# SPE_PHY.net
KiCad netlist of a schematic drawn in Altium Designer
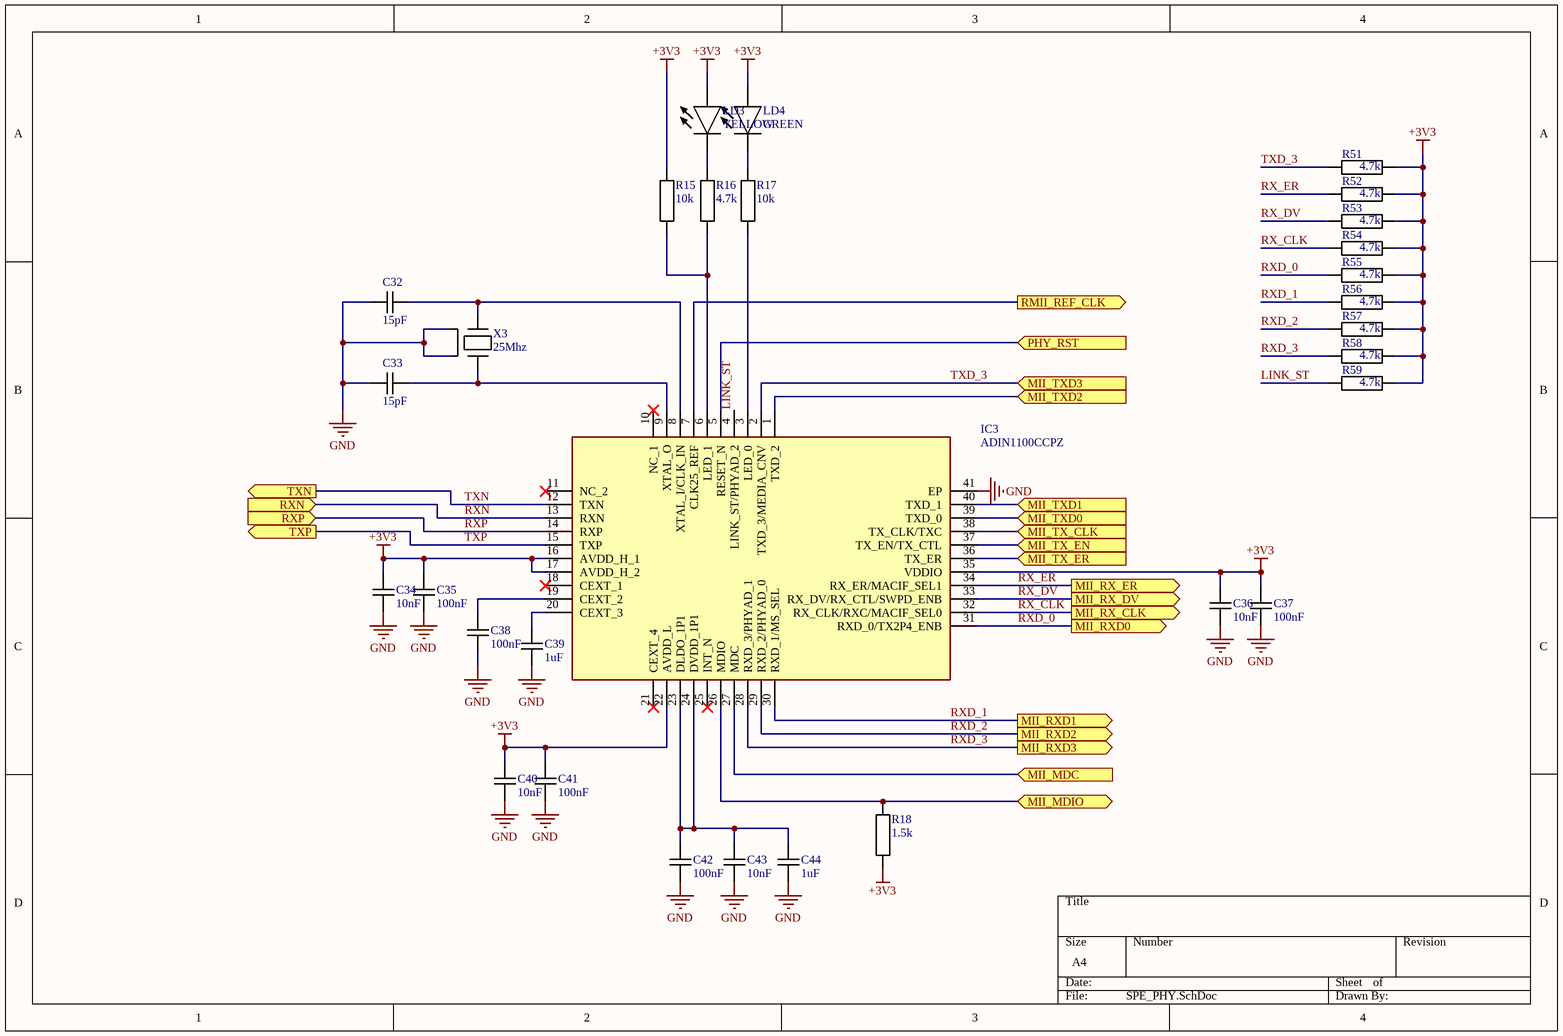
[diagram p0: SPE_PHY.SchDoc]

(export (version "E")
  (design (tool "Eeschema 10.0.6"))
  (components
    (comp (ref "C32")
      (value "15pF")
      (footprint "CAPACITOR 1608 REFLOW")
      (description "Capacitor")
      (libsource (lib "Capacitor") (part "Capacitor"))
    )
    (comp (ref "C33")
      (value "15pF")
      (footprint "CAPACITOR 1608 REFLOW")
      (description "Capacitor")
      (libsource (lib "Capacitor") (part "Capacitor"))
    )
    (comp (ref "C34")
      (value "10nF")
      (footprint "CAPACITOR 1608 REFLOW")
      (description "Capacitor")
      (libsource (lib "Capacitor") (part "Capacitor"))
    )
    (comp (ref "C35")
      (value "100nF")
      (footprint "CAPACITOR 1608 REFLOW")
      (description "Capacitor")
      (libsource (lib "Capacitor") (part "Capacitor"))
    )
    (comp (ref "C36")
      (value "10nF")
      (footprint "CAPACITOR 1608 REFLOW")
      (description "Capacitor")
      (libsource (lib "Capacitor") (part "Capacitor"))
    )
    (comp (ref "C37")
      (value "100nF")
      (footprint "CAPACITOR 1608 REFLOW")
      (description "Capacitor")
      (libsource (lib "Capacitor") (part "Capacitor"))
    )
    (comp (ref "C38")
      (value "100nF")
      (footprint "CAPACITOR 1608 REFLOW")
      (description "Capacitor")
      (libsource (lib "Capacitor") (part "Capacitor"))
    )
    (comp (ref "C39")
      (value "1uF")
      (footprint "CAPACITOR 1608 REFLOW")
      (description "Capacitor")
      (libsource (lib "Capacitor") (part "Capacitor"))
    )
    (comp (ref "C40")
      (value "10nF")
      (footprint "CAPACITOR 1608 REFLOW")
      (description "Capacitor")
      (libsource (lib "Capacitor") (part "Capacitor"))
    )
    (comp (ref "C41")
      (value "100nF")
      (footprint "CAPACITOR 1608 REFLOW")
      (description "Capacitor")
      (libsource (lib "Capacitor") (part "Capacitor"))
    )
    (comp (ref "C42")
      (value "100nF")
      (footprint "CAPACITOR 1608 REFLOW")
      (description "Capacitor")
      (libsource (lib "Capacitor") (part "Capacitor"))
    )
    (comp (ref "C43")
      (value "10nF")
      (footprint "CAPACITOR 1608 REFLOW")
      (description "Capacitor")
      (libsource (lib "Capacitor") (part "Capacitor"))
    )
    (comp (ref "C44")
      (value "1uF")
      (footprint "CAPACITOR 1608 REFLOW")
      (description "Capacitor")
      (libsource (lib "Capacitor") (part "Capacitor"))
    )
    (comp (ref "IC3")
      (value "ADIN1100CCPZ")
      (footprint "QFN50P600X600X80-41N-D")
      (description "Integrated Circuit")
      (fields (field (name "MOUSER PART NUMBER") "584-ADIN1100CCPZ"))
      (libsource (lib "*") (part "ADIN1100CCPZ"))
    )
    (comp (ref "LD3")
      (value "YELLOW")
      (footprint "LED 1608 REFLOW")
      (description "LED generic")
      (libsource (lib "Diode") (part "LED"))
    )
    (comp (ref "LD4")
      (value "GREEN")
      (footprint "LED 1608 REFLOW")
      (description "LED generic")
      (libsource (lib "Diode") (part "LED"))
    )
    (comp (ref "R15")
      (value "10k")
      (footprint "RESISTOR 1608 REFLOW")
      (description "Resistor")
      (libsource (lib "Resistor") (part "Resistor"))
    )
    (comp (ref "R16")
      (value "4.7k")
      (footprint "RESISTOR 1608 REFLOW")
      (description "Resistor")
      (libsource (lib "Resistor") (part "Resistor"))
    )
    (comp (ref "R17")
      (value "10k")
      (footprint "RESISTOR 1608 REFLOW")
      (description "Resistor")
      (libsource (lib "Resistor") (part "Resistor"))
    )
    (comp (ref "R18")
      (value "1.5k")
      (footprint "RESISTOR 1608 REFLOW")
      (description "Resistor")
      (libsource (lib "Resistor") (part "Resistor"))
    )
    (comp (ref "R51")
      (value "4.7k")
      (footprint "RESISTOR 1608 REFLOW")
      (description "Resistor")
      (libsource (lib "Resistor") (part "Resistor"))
    )
    (comp (ref "R52")
      (value "4.7k")
      (footprint "RESISTOR 1608 REFLOW")
      (description "Resistor")
      (libsource (lib "Resistor") (part "Resistor"))
    )
    (comp (ref "R53")
      (value "4.7k")
      (footprint "RESISTOR 1608 REFLOW")
      (description "Resistor")
      (libsource (lib "Resistor") (part "Resistor"))
    )
    (comp (ref "R54")
      (value "4.7k")
      (footprint "RESISTOR 1608 REFLOW")
      (description "Resistor")
      (libsource (lib "Resistor") (part "Resistor"))
    )
    (comp (ref "R55")
      (value "4.7k")
      (footprint "RESISTOR 1608 REFLOW")
      (description "Resistor")
      (libsource (lib "Resistor") (part "Resistor"))
    )
    (comp (ref "R56")
      (value "4.7k")
      (footprint "RESISTOR 1608 REFLOW")
      (description "Resistor")
      (libsource (lib "Resistor") (part "Resistor"))
    )
    (comp (ref "R57")
      (value "4.7k")
      (footprint "RESISTOR 1608 REFLOW")
      (description "Resistor")
      (libsource (lib "Resistor") (part "Resistor"))
    )
    (comp (ref "R58")
      (value "4.7k")
      (footprint "RESISTOR 1608 REFLOW")
      (description "Resistor")
      (libsource (lib "Resistor") (part "Resistor"))
    )
    (comp (ref "R59")
      (value "4.7k")
      (footprint "RESISTOR 1608 REFLOW")
      (description "Resistor")
      (libsource (lib "Resistor") (part "Resistor"))
    )
    (comp (ref "X3")
      (value "25Mhz")
      (footprint "Crystal C2.5x2 Seiko Epson FA-128")
      (description "Crystal C2.5x2 Seiko Epson FA-128")
      (libsource (lib "Oscillator") (part "Crystal C2.5x2 Seiko Epson FA-128"))
    )
  )
  (nets
    (net (code "1") (name "+3V3") (class "Default")
      (node (ref "C34") (pin "2") (pinfunction "2_2") (pintype "passive"))
      (node (ref "C35") (pin "2") (pinfunction "2_2") (pintype "passive"))
      (node (ref "C36") (pin "2") (pinfunction "2_2") (pintype "passive"))
      (node (ref "C37") (pin "2") (pinfunction "2_2") (pintype "passive"))
      (node (ref "C40") (pin "2") (pinfunction "2_2") (pintype "passive"))
      (node (ref "C41") (pin "2") (pinfunction "2_2") (pintype "passive"))
      (node (ref "IC3") (pin "16") (pinfunction "AVDD_H_1_16") (pintype "passive"))
      (node (ref "IC3") (pin "17") (pinfunction "AVDD_H_2_17") (pintype "passive"))
      (node (ref "IC3") (pin "22") (pinfunction "AVDD_L_22") (pintype "passive"))
      (node (ref "IC3") (pin "35") (pinfunction "VDDIO_35") (pintype "passive"))
      (node (ref "LD3") (pin "2") (pinfunction "A_2") (pintype "passive"))
      (node (ref "LD4") (pin "2") (pinfunction "A_2") (pintype "passive"))
      (node (ref "R15") (pin "2") (pinfunction "2_2") (pintype "passive"))
      (node (ref "R18") (pin "1") (pinfunction "1_1") (pintype "passive"))
      (node (ref "R51") (pin "1") (pinfunction "1_1") (pintype "passive"))
      (node (ref "R52") (pin "1") (pinfunction "1_1") (pintype "passive"))
      (node (ref "R53") (pin "1") (pinfunction "1_1") (pintype "passive"))
      (node (ref "R54") (pin "1") (pinfunction "1_1") (pintype "passive"))
      (node (ref "R55") (pin "1") (pinfunction "1_1") (pintype "passive"))
      (node (ref "R56") (pin "1") (pinfunction "1_1") (pintype "passive"))
      (node (ref "R57") (pin "1") (pinfunction "1_1") (pintype "passive"))
      (node (ref "R58") (pin "1") (pinfunction "1_1") (pintype "passive"))
      (node (ref "R59") (pin "1") (pinfunction "1_1") (pintype "passive"))
    )
    (net (code "2") (name "/LINK_ST") (class "Default")
      (node (ref "IC3") (pin "4") (pinfunction "LINK_ST/PHYAD_2_4") (pintype "passive"))
      (node (ref "R59") (pin "2") (pinfunction "2_2") (pintype "passive"))
    )
    (net (code "3") (name "/MII_MDC") (class "Default")
      (node (ref "IC3") (pin "27") (pinfunction "MDC_27") (pintype "passive"))
    )
    (net (code "4") (name "/MII_MDIO") (class "Default")
      (node (ref "IC3") (pin "26") (pinfunction "MDIO_26") (pintype "passive"))
      (node (ref "R18") (pin "2") (pinfunction "2_2") (pintype "passive"))
    )
    (net (code "5") (name "/MII_TXD0") (class "Default")
      (node (ref "IC3") (pin "39") (pinfunction "TXD_0_39") (pintype "passive"))
    )
    (net (code "6") (name "/MII_TXD1") (class "Default")
      (node (ref "IC3") (pin "40") (pinfunction "TXD_1_40") (pintype "passive"))
    )
    (net (code "7") (name "/MII_TXD2") (class "Default")
      (node (ref "IC3") (pin "1") (pinfunction "TXD_2_1") (pintype "passive"))
    )
    (net (code "8") (name "/MII_TX_CLK") (class "Default")
      (node (ref "IC3") (pin "38") (pinfunction "TX_CLK/TXC_38") (pintype "passive"))
    )
    (net (code "9") (name "/MII_TX_EN") (class "Default")
      (node (ref "IC3") (pin "37") (pinfunction "TX_EN/TX_CTL_37") (pintype "passive"))
    )
    (net (code "10") (name "/MII_TX_ER") (class "Default")
      (node (ref "IC3") (pin "36") (pinfunction "TX_ER_36") (pintype "passive"))
    )
    (net (code "11") (name "/PHY_RST") (class "Default")
      (node (ref "IC3") (pin "5") (pinfunction "RESET_N_5") (pintype "passive"))
    )
    (net (code "12") (name "/RMII_REF_CLK") (class "Default")
      (node (ref "IC3") (pin "7") (pinfunction "CLK25_REF_7") (pintype "passive"))
    )
    (net (code "13") (name "/RXD_0") (class "Default")
      (node (ref "IC3") (pin "31") (pinfunction "RXD_0/TX2P4_ENB_31") (pintype "passive"))
      (node (ref "R55") (pin "2") (pinfunction "2_2") (pintype "passive"))
    )
    (net (code "14") (name "/RXD_1") (class "Default")
      (node (ref "IC3") (pin "30") (pinfunction "RXD_1/MS_SEL_30") (pintype "passive"))
      (node (ref "R56") (pin "2") (pinfunction "2_2") (pintype "passive"))
    )
    (net (code "15") (name "/RXD_2") (class "Default")
      (node (ref "IC3") (pin "29") (pinfunction "RXD_2/PHYAD_0_29") (pintype "passive"))
      (node (ref "R57") (pin "2") (pinfunction "2_2") (pintype "passive"))
    )
    (net (code "16") (name "/RXD_3") (class "Default")
      (node (ref "IC3") (pin "28") (pinfunction "RXD_3/PHYAD_1_28") (pintype "passive"))
      (node (ref "R58") (pin "2") (pinfunction "2_2") (pintype "passive"))
    )
    (net (code "17") (name "/RXN") (class "Default")
      (node (ref "IC3") (pin "13") (pinfunction "RXN_13") (pintype "passive"))
    )
    (net (code "18") (name "/RXP") (class "Default")
      (node (ref "IC3") (pin "14") (pinfunction "RXP_14") (pintype "passive"))
    )
    (net (code "19") (name "/RX_CLK") (class "Default")
      (node (ref "IC3") (pin "32") (pinfunction "RX_CLK/RXC/MACIF_SEL0_32") (pintype "passive"))
      (node (ref "R54") (pin "2") (pinfunction "2_2") (pintype "passive"))
    )
    (net (code "20") (name "/RX_DV") (class "Default")
      (node (ref "IC3") (pin "33") (pinfunction "RX_DV/RX_CTL/SWPD_ENB_33") (pintype "passive"))
      (node (ref "R53") (pin "2") (pinfunction "2_2") (pintype "passive"))
    )
    (net (code "21") (name "/RX_ER") (class "Default")
      (node (ref "IC3") (pin "34") (pinfunction "RX_ER/MACIF_SEL1_34") (pintype "passive"))
      (node (ref "R52") (pin "2") (pinfunction "2_2") (pintype "passive"))
    )
    (net (code "22") (name "/TXD_3") (class "Default")
      (node (ref "IC3") (pin "2") (pinfunction "TXD_3/MEDIA_CNV_2") (pintype "passive"))
      (node (ref "R51") (pin "2") (pinfunction "2_2") (pintype "passive"))
    )
    (net (code "23") (name "/TXN") (class "Default")
      (node (ref "IC3") (pin "12") (pinfunction "TXN_12") (pintype "passive"))
    )
    (net (code "24") (name "/TXP") (class "Default")
      (node (ref "IC3") (pin "15") (pinfunction "TXP_15") (pintype "passive"))
    )
    (net (code "25") (name "GND") (class "Default")
      (node (ref "C32") (pin "2") (pinfunction "2_2") (pintype "passive"))
      (node (ref "C33") (pin "2") (pinfunction "2_2") (pintype "passive"))
      (node (ref "C34") (pin "1") (pinfunction "1_1") (pintype "passive"))
      (node (ref "C35") (pin "1") (pinfunction "1_1") (pintype "passive"))
      (node (ref "C36") (pin "1") (pinfunction "1_1") (pintype "passive"))
      (node (ref "C37") (pin "1") (pinfunction "1_1") (pintype "passive"))
      (node (ref "C38") (pin "1") (pinfunction "1_1") (pintype "passive"))
      (node (ref "C39") (pin "1") (pinfunction "1_1") (pintype "passive"))
      (node (ref "C40") (pin "1") (pinfunction "1_1") (pintype "passive"))
      (node (ref "C41") (pin "1") (pinfunction "1_1") (pintype "passive"))
      (node (ref "C42") (pin "1") (pinfunction "1_1") (pintype "passive"))
      (node (ref "C43") (pin "1") (pinfunction "1_1") (pintype "passive"))
      (node (ref "C44") (pin "1") (pinfunction "1_1") (pintype "passive"))
      (node (ref "IC3") (pin "41") (pinfunction "EP_41") (pintype "passive"))
      (node (ref "X3") (pin "2") (pinfunction "2_2") (pintype "passive"))
      (node (ref "X3") (pin "4") (pinfunction "4_4") (pintype "passive"))
    )
    (net (code "26") (name "Net-(IC3-CEXT_2)") (class "Default")
      (node (ref "C38") (pin "2") (pinfunction "2_2") (pintype "passive"))
      (node (ref "IC3") (pin "19") (pinfunction "CEXT_2_19") (pintype "passive"))
    )
    (net (code "27") (name "Net-(IC3-CEXT_3)") (class "Default")
      (node (ref "C39") (pin "2") (pinfunction "2_2") (pintype "passive"))
      (node (ref "IC3") (pin "20") (pinfunction "CEXT_3_20") (pintype "passive"))
    )
    (net (code "28") (name "Net-(IC3-DLDO_1P1)") (class "Default")
      (node (ref "C42") (pin "2") (pinfunction "2_2") (pintype "passive"))
      (node (ref "C43") (pin "2") (pinfunction "2_2") (pintype "passive"))
      (node (ref "C44") (pin "2") (pinfunction "2_2") (pintype "passive"))
      (node (ref "IC3") (pin "23") (pinfunction "DLDO_1P1_23") (pintype "passive"))
      (node (ref "IC3") (pin "24") (pinfunction "DVDD_1P1_24") (pintype "passive"))
    )
    (net (code "29") (name "Net-(IC3-LED_0)") (class "Default")
      (node (ref "IC3") (pin "3") (pinfunction "LED_0_3") (pintype "passive"))
      (node (ref "R17") (pin "1") (pinfunction "1_1") (pintype "passive"))
    )
    (net (code "30") (name "Net-(IC3-LED_1)") (class "Default")
      (node (ref "IC3") (pin "6") (pinfunction "LED_1_6") (pintype "passive"))
      (node (ref "R15") (pin "1") (pinfunction "1_1") (pintype "passive"))
      (node (ref "R16") (pin "1") (pinfunction "1_1") (pintype "passive"))
    )
    (net (code "31") (name "Net-(IC3-XTAL_I{slash}CLK_IN)") (class "Default")
      (node (ref "C32") (pin "1") (pinfunction "1_1") (pintype "passive"))
      (node (ref "IC3") (pin "8") (pinfunction "XTAL_I/CLK_IN_8") (pintype "passive"))
      (node (ref "X3") (pin "1") (pinfunction "1_1") (pintype "passive"))
    )
    (net (code "32") (name "Net-(IC3-XTAL_O)") (class "Default")
      (node (ref "C33") (pin "1") (pinfunction "1_1") (pintype "passive"))
      (node (ref "IC3") (pin "9") (pinfunction "XTAL_O_9") (pintype "passive"))
      (node (ref "X3") (pin "3") (pinfunction "3_3") (pintype "passive"))
    )
    (net (code "33") (name "Net-(LD3-C)") (class "Default")
      (node (ref "LD3") (pin "1") (pinfunction "C_1") (pintype "passive"))
      (node (ref "R16") (pin "2") (pinfunction "2_2") (pintype "passive"))
    )
    (net (code "34") (name "Net-(LD4-C)") (class "Default")
      (node (ref "LD4") (pin "1") (pinfunction "C_1") (pintype "passive"))
      (node (ref "R17") (pin "2") (pinfunction "2_2") (pintype "passive"))
    )
    (net (code "35") (name "unconnected-(IC3-CEXT_1-Pad18)") (class "Default")
      (node (ref "IC3") (pin "18") (pinfunction "CEXT_1_18") (pintype "passive+no_connect"))
    )
    (net (code "36") (name "unconnected-(IC3-CEXT_4-Pad21)") (class "Default")
      (node (ref "IC3") (pin "21") (pinfunction "CEXT_4_21") (pintype "passive+no_connect"))
    )
    (net (code "37") (name "unconnected-(IC3-INT_N-Pad25)") (class "Default")
      (node (ref "IC3") (pin "25") (pinfunction "INT_N_25") (pintype "passive+no_connect"))
    )
    (net (code "38") (name "unconnected-(IC3-NC_1-Pad10)") (class "Default")
      (node (ref "IC3") (pin "10") (pinfunction "NC_1_10") (pintype "passive+no_connect"))
    )
    (net (code "39") (name "unconnected-(IC3-NC_2-Pad11)") (class "Default")
      (node (ref "IC3") (pin "11") (pinfunction "NC_2_11") (pintype "passive+no_connect"))
    )
  )
)
